# interface.net
KiCad netlist of a schematic drawn in Altium Designer
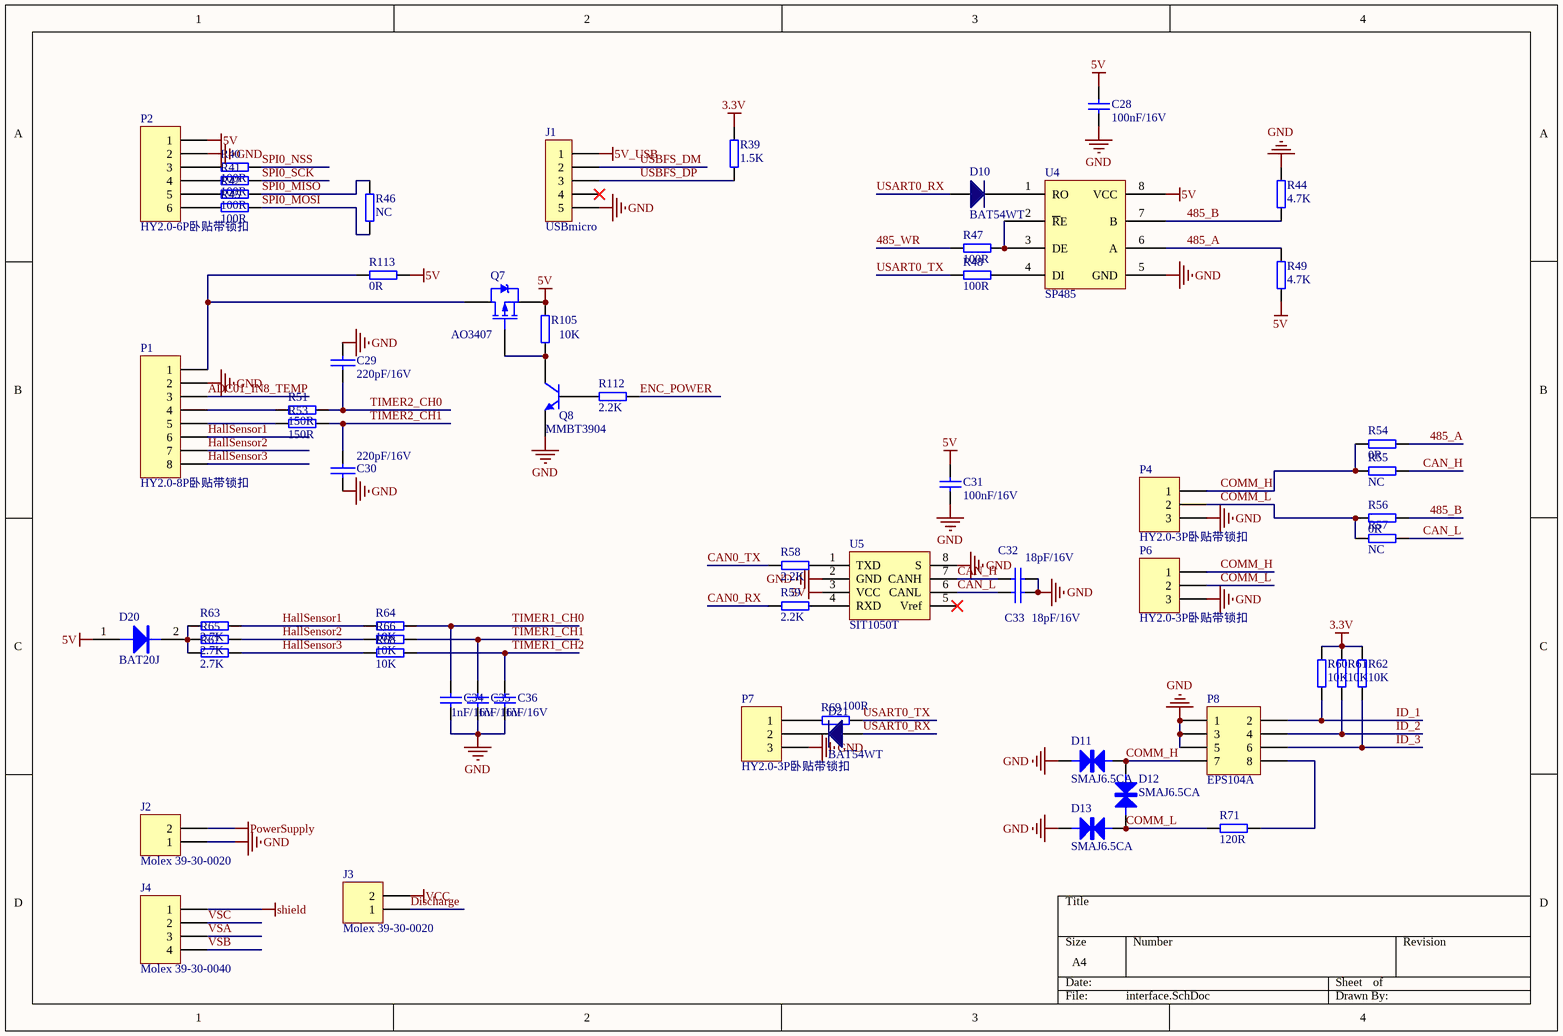
[diagram p0: interface.SchDoc]

(export (version "E")
  (design (tool "Eeschema 10.0.6"))
  (components
    (comp (ref "C28") (value "100nF/16V") (footprint "C0402") (libsource (lib "zijianku") (part "cap")))
    (comp (ref "C29")
      (value "220pF/16V")
      (footprint "C0402")
      (description "Capacitor")
      (libsource (lib "*") (part "CAP"))
    )
    (comp (ref "C30")
      (value "220pF/16V")
      (footprint "C0402")
      (description "Capacitor")
      (libsource (lib "*") (part "CAP"))
    )
    (comp (ref "C31") (value "100nF/16V") (footprint "C0402") (libsource (lib "zijianku") (part "cap")))
    (comp (ref "C32") (value "18pF/16V") (footprint "C0402") (libsource (lib "zijianku") (part "cap")))
    (comp (ref "C33") (value "18pF/16V") (footprint "C0402") (libsource (lib "zijianku") (part "cap")))
    (comp (ref "C34") (value "1nF/16V") (footprint "C0402") (libsource (lib "zijianku") (part "cap")))
    (comp (ref "C35") (value "1nF/16V") (footprint "C0402") (libsource (lib "zijianku") (part "cap")))
    (comp (ref "C36") (value "1nF/16V") (footprint "C0402") (libsource (lib "zijianku") (part "cap")))
    (comp (ref "D10")
      (value "BAT54WT")
      (footprint "SOD-523/SC-79")
      (libsource (lib "Common Device") (part "Diode"))
    )
    (comp (ref "D11")
      (value "SMAJ6.5CA")
      (footprint "DO-214AC SMA")
      (libsource (lib "zijianku") (part "Bi-DIODES"))
    )
    (comp (ref "D12")
      (value "SMAJ6.5CA")
      (footprint "DO-214AC SMA")
      (libsource (lib "") (part "Bi-DIODES_1"))
    )
    (comp (ref "D13")
      (value "SMAJ6.5CA")
      (footprint "DO-214AC SMA")
      (libsource (lib "zijianku") (part "Bi-DIODES"))
    )
    (comp (ref "D20") (value "BAT20J") (footprint "SOD-323") (libsource (lib "*") (part "DIODE")))
    (comp (ref "D21")
      (value "BAT54WT")
      (footprint "SOD-523/SC-79")
      (libsource (lib "Common Device") (part "Diode"))
    )
    (comp (ref "J1")
      (value "USBmicro")
      (footprint "USBmicro")
      (description "USB micro母座")
      (libsource (lib "*") (part "CON5"))
    )
    (comp (ref "J2")
      (value "Molex 39-30-0020")
      (footprint "Molex 39-30-0020")
      (description "Header, 2-Pin")
      (fields (field (name "PUBLISHER") "Altium Limited"))
      (libsource (lib "Common Headers") (part "Header 2"))
    )
    (comp (ref "J3")
      (value "Molex 39-30-0020")
      (footprint "Molex 39-30-0020")
      (description "Header, 2-Pin")
      (fields (field (name "PUBLISHER") "Altium Limited"))
      (libsource (lib "Common Headers") (part "Header 2"))
    )
    (comp (ref "J4")
      (value "Molex 39-30-0040")
      (footprint "Molex 39-30-0040")
      (description "Header, 4-Pin")
      (fields (field (name "PUBLISHER") "Altium Limited"))
      (libsource (lib "Common Headers") (part "Header 4"))
    )
    (comp (ref "P1")
      (value "HY2.0-8P卧贴带锁扣")
      (footprint "2.0-8PIN 卧式")
      (fields (field (name "PUBLISHER") "Altium Limited"))
      (libsource (lib "Common Headers") (part "Header 8"))
    )
    (comp (ref "P2")
      (value "HY2.0-6P卧贴带锁扣")
      (footprint "2.0-6PIN 卧式")
      (fields (field (name "PUBLISHER") "Altium Limited"))
      (libsource (lib "Common Headers") (part "Header 6"))
    )
    (comp (ref "P4")
      (value "HY2.0-3P卧贴带锁扣")
      (footprint "2.0-3PIN 卧式")
      (fields (field (name "PUBLISHER") "Altium Limited"))
      (libsource (lib "Common Headers") (part "Header 3"))
    )
    (comp (ref "P6")
      (value "HY2.0-3P卧贴带锁扣")
      (footprint "2.0-3PIN 卧式")
      (fields (field (name "PUBLISHER") "Altium Limited"))
      (libsource (lib "Common Headers") (part "Header 3"))
    )
    (comp (ref "P7")
      (value "HY2.0-3P卧贴带锁扣")
      (footprint "2.0-3PIN 卧式")
      (fields (field (name "PUBLISHER") "Altium Limited"))
      (libsource (lib "Common Headers") (part "Header 3"))
    )
    (comp (ref "P8")
      (value "EPS104A")
      (footprint "EPG104A")
      (description "侧拨程式开关 2.54间距 4PIN 品牌：台湾ECE")
      (fields (field (name "PUBLISHER") "Altium Limited"))
      (libsource (lib "Common Headers") (part "Header 4X2"))
    )
    (comp (ref "Q7")
      (value "AO3407")
      (footprint "SOT-23")
      (libsource (lib "zijianku") (part "P-channel Enhancement MOS"))
    )
    (comp (ref "Q8") (value "MMBT3904") (footprint "SOT-23") (libsource (lib "zijianku") (part "NPN")))
    (comp (ref "R39") (value "1.5K") (footprint "R0402") (libsource (lib "zijianku") (part "Resistance")))
    (comp (ref "R40") (value "100R") (footprint "R0402") (libsource (lib "zijianku") (part "Resistance")))
    (comp (ref "R41") (value "100R") (footprint "R0402") (libsource (lib "zijianku") (part "Resistance")))
    (comp (ref "R42") (value "100R") (footprint "R0402") (libsource (lib "zijianku") (part "Resistance")))
    (comp (ref "R44") (value "4.7K") (footprint "R0402") (libsource (lib "zijianku") (part "Resistance")))
    (comp (ref "R45") (value "100R") (footprint "R0402") (libsource (lib "zijianku") (part "Resistance")))
    (comp (ref "R46") (value "NC") (footprint "R0603") (libsource (lib "zijianku") (part "Resistance")))
    (comp (ref "R47") (value "100R") (footprint "R0402") (libsource (lib "zijianku") (part "Resistance")))
    (comp (ref "R48") (value "100R") (footprint "R0402") (libsource (lib "zijianku") (part "Resistance")))
    (comp (ref "R49") (value "4.7K") (footprint "R0402") (libsource (lib "zijianku") (part "Resistance")))
    (comp (ref "R51") (value "150R") (footprint "R0402") (libsource (lib "zijianku") (part "Resistance")))
    (comp (ref "R53") (value "150R") (footprint "R0402") (libsource (lib "zijianku") (part "Resistance")))
    (comp (ref "R54") (value "0R") (footprint "R0603") (libsource (lib "zijianku") (part "Resistance")))
    (comp (ref "R55") (value "NC") (footprint "R0603") (libsource (lib "zijianku") (part "Resistance")))
    (comp (ref "R56") (value "0R") (footprint "R0603") (libsource (lib "zijianku") (part "Resistance")))
    (comp (ref "R57") (value "NC") (footprint "R0603") (libsource (lib "zijianku") (part "Resistance")))
    (comp (ref "R58") (value "2.2K") (footprint "R0402") (libsource (lib "zijianku") (part "Resistance")))
    (comp (ref "R59") (value "2.2K") (footprint "R0402") (libsource (lib "zijianku") (part "Resistance")))
    (comp (ref "R60") (value "10K") (footprint "R0402") (libsource (lib "zijianku") (part "Resistance")))
    (comp (ref "R61") (value "10K") (footprint "R0402") (libsource (lib "zijianku") (part "Resistance")))
    (comp (ref "R62") (value "10K") (footprint "R0402") (libsource (lib "zijianku") (part "Resistance")))
    (comp (ref "R63") (value "2.7K") (footprint "R0402") (libsource (lib "zijianku") (part "Resistance")))
    (comp (ref "R64") (value "10K") (footprint "R0402") (libsource (lib "zijianku") (part "Resistance")))
    (comp (ref "R65") (value "2.7K") (footprint "R0402") (libsource (lib "zijianku") (part "Resistance")))
    (comp (ref "R66") (value "10K") (footprint "R0402") (libsource (lib "zijianku") (part "Resistance")))
    (comp (ref "R67") (value "2.7K") (footprint "R0402") (libsource (lib "zijianku") (part "Resistance")))
    (comp (ref "R68") (value "10K") (footprint "R0402") (libsource (lib "zijianku") (part "Resistance")))
    (comp (ref "R69") (value "100R") (footprint "R0402") (libsource (lib "zijianku") (part "Resistance")))
    (comp (ref "R71") (value "120R") (footprint "R0603") (libsource (lib "zijianku") (part "Resistance")))
    (comp (ref "R105") (value "10K") (footprint "R0402") (libsource (lib "zijianku") (part "Resistance")))
    (comp (ref "R112") (value "2.2K") (footprint "R0402") (libsource (lib "zijianku") (part "Resistance")))
    (comp (ref "R113") (value "0R") (footprint "R0805") (libsource (lib "zijianku") (part "Resistance")))
    (comp (ref "U4") (value "SP485") (footprint "SOIC-8") (libsource (lib "zijianku") (part "SP485")))
    (comp (ref "U5")
      (value "SIT1050T")
      (footprint "SOIC-8")
      (libsource (lib "Common Device") (part "TJA1050"))
    )
  )
  (nets
    (net (code "1") (name "/485_A") (class "Default")
      (node (ref "R49") (pin "2") (pintype "passive"))
      (node (ref "R54") (pin "1") (pintype "passive"))
      (node (ref "U4") (pin "6") (pinfunction "A_6") (pintype "passive"))
    )
    (net (code "2") (name "/485_B") (class "Default")
      (node (ref "R44") (pin "1") (pintype "passive"))
      (node (ref "R56") (pin "1") (pintype "passive"))
      (node (ref "U4") (pin "7") (pinfunction "B_7") (pintype "passive"))
    )
    (net (code "3") (name "/485_WR") (class "Default") (node (ref "R47") (pin "2") (pintype "passive")))
    (net (code "4") (name "/ADC01_IN8_TEMP") (class "Default")
      (node (ref "P1") (pin "3") (pinfunction "3_3") (pintype "passive"))
    )
    (net (code "5") (name "/CAN0_RX") (class "Default") (node (ref "R59") (pin "2") (pintype "passive")))
    (net (code "6") (name "/CAN0_TX") (class "Default") (node (ref "R58") (pin "2") (pintype "passive")))
    (net (code "7") (name "/CAN_H") (class "Default")
      (node (ref "C32") (pin "2") (pinfunction "1_2") (pintype "passive"))
      (node (ref "R55") (pin "1") (pintype "passive"))
      (node (ref "U5") (pin "7") (pinfunction "CANH_7") (pintype "passive"))
    )
    (net (code "8") (name "/CAN_L") (class "Default")
      (node (ref "C33") (pin "2") (pinfunction "1_2") (pintype "passive"))
      (node (ref "R57") (pin "1") (pintype "passive"))
      (node (ref "U5") (pin "6") (pinfunction "CANL_6") (pintype "passive"))
    )
    (net (code "9") (name "/COMM_H") (class "Default")
      (node (ref "D11") (pin "2") (pinfunction "Anode_2") (pintype "passive"))
      (node (ref "D12") (pin "1") (pinfunction "Anode_1") (pintype "passive"))
      (node (ref "P4") (pin "1") (pinfunction "1_1") (pintype "passive"))
      (node (ref "P6") (pin "1") (pinfunction "1_1") (pintype "passive"))
      (node (ref "P8") (pin "7") (pinfunction "7_7") (pintype "passive"))
      (node (ref "R54") (pin "2") (pintype "passive"))
      (node (ref "R55") (pin "2") (pintype "passive"))
    )
    (net (code "10") (name "/COMM_L") (class "Default")
      (node (ref "D12") (pin "2") (pinfunction "Anode_2") (pintype "passive"))
      (node (ref "D13") (pin "2") (pinfunction "Anode_2") (pintype "passive"))
      (node (ref "P4") (pin "2") (pinfunction "2_2") (pintype "passive"))
      (node (ref "P6") (pin "2") (pinfunction "2_2") (pintype "passive"))
      (node (ref "R56") (pin "2") (pintype "passive"))
      (node (ref "R57") (pin "2") (pintype "passive"))
      (node (ref "R71") (pin "2") (pintype "passive"))
    )
    (net (code "11") (name "/Discharge") (class "Default")
      (node (ref "J3") (pin "1") (pinfunction "1_1") (pintype "passive"))
    )
    (net (code "12") (name "/ENC_POWER") (class "Default") (node (ref "R112") (pin "2") (pintype "passive")))
    (net (code "13") (name "/HallSensor1") (class "Default")
      (node (ref "P1") (pin "6") (pinfunction "6_6") (pintype "passive"))
      (node (ref "R63") (pin "1") (pintype "passive"))
      (node (ref "R64") (pin "1") (pintype "passive"))
    )
    (net (code "14") (name "/HallSensor2") (class "Default")
      (node (ref "P1") (pin "7") (pinfunction "7_7") (pintype "passive"))
      (node (ref "R65") (pin "1") (pintype "passive"))
      (node (ref "R66") (pin "1") (pintype "passive"))
    )
    (net (code "15") (name "/HallSensor3") (class "Default")
      (node (ref "P1") (pin "8") (pinfunction "8_8") (pintype "passive"))
      (node (ref "R67") (pin "1") (pintype "passive"))
      (node (ref "R68") (pin "1") (pintype "passive"))
    )
    (net (code "16") (name "/ID_1") (class "Default")
      (node (ref "P8") (pin "2") (pinfunction "2_2") (pintype "passive"))
      (node (ref "R60") (pin "1") (pintype "passive"))
    )
    (net (code "17") (name "/ID_2") (class "Default")
      (node (ref "P8") (pin "4") (pinfunction "4_4") (pintype "passive"))
      (node (ref "R61") (pin "1") (pintype "passive"))
    )
    (net (code "18") (name "/ID_3") (class "Default")
      (node (ref "P8") (pin "6") (pinfunction "6_6") (pintype "passive"))
      (node (ref "R62") (pin "1") (pintype "passive"))
    )
    (net (code "19") (name "/SPI0_MISO") (class "Default")
      (node (ref "R42") (pin "1") (pintype "passive"))
      (node (ref "R46") (pin "1") (pintype "passive"))
    )
    (net (code "20") (name "/SPI0_MOSI") (class "Default")
      (node (ref "R45") (pin "1") (pintype "passive"))
      (node (ref "R46") (pin "2") (pintype "passive"))
    )
    (net (code "21") (name "/SPI0_NSS") (class "Default") (node (ref "R40") (pin "1") (pintype "passive")))
    (net (code "22") (name "/SPI0_SCK") (class "Default") (node (ref "R41") (pin "1") (pintype "passive")))
    (net (code "23") (name "/TIMER1_CH0") (class "Default")
      (node (ref "C34") (pin "1") (pinfunction "0_1") (pintype "passive"))
      (node (ref "R64") (pin "2") (pintype "passive"))
    )
    (net (code "24") (name "/TIMER1_CH1") (class "Default")
      (node (ref "C35") (pin "1") (pinfunction "0_1") (pintype "passive"))
      (node (ref "R66") (pin "2") (pintype "passive"))
    )
    (net (code "25") (name "/TIMER1_CH2") (class "Default")
      (node (ref "C36") (pin "1") (pinfunction "0_1") (pintype "passive"))
      (node (ref "R68") (pin "2") (pintype "passive"))
    )
    (net (code "26") (name "/TIMER2_CH0") (class "Default")
      (node (ref "C29") (pin "1") (pinfunction "1_1") (pintype "passive"))
      (node (ref "R51") (pin "2") (pintype "passive"))
    )
    (net (code "27") (name "/TIMER2_CH1") (class "Default")
      (node (ref "C30") (pin "2") (pinfunction "2_2") (pintype "passive"))
      (node (ref "R53") (pin "2") (pintype "passive"))
    )
    (net (code "28") (name "/USART0_RX") (class "Default")
      (node (ref "D10") (pin "1") (pinfunction "0_1") (pintype "passive"))
      (node (ref "D21") (pin "1") (pinfunction "0_1") (pintype "passive"))
    )
    (net (code "29") (name "/USART0_TX") (class "Default")
      (node (ref "R48") (pin "2") (pintype "passive"))
      (node (ref "R69") (pin "1") (pintype "passive"))
    )
    (net (code "30") (name "/USBFS_DM") (class "Default")
      (node (ref "J1") (pin "2") (pinfunction "2_2") (pintype "passive"))
    )
    (net (code "31") (name "/USBFS_DP") (class "Default")
      (node (ref "J1") (pin "3") (pinfunction "3_3") (pintype "passive"))
      (node (ref "R39") (pin "1") (pintype "passive"))
    )
    (net (code "32") (name "/VSA") (class "Default")
      (node (ref "J4") (pin "3") (pinfunction "3_3") (pintype "passive"))
    )
    (net (code "33") (name "/VSB") (class "Default")
      (node (ref "J4") (pin "4") (pinfunction "4_4") (pintype "passive"))
    )
    (net (code "34") (name "/VSC") (class "Default")
      (node (ref "J4") (pin "2") (pinfunction "2_2") (pintype "passive"))
    )
    (net (code "35") (name "3.3V") (class "Default")
      (node (ref "R39") (pin "2") (pintype "passive"))
      (node (ref "R60") (pin "2") (pintype "passive"))
      (node (ref "R61") (pin "2") (pintype "passive"))
      (node (ref "R62") (pin "2") (pintype "passive"))
    )
    (net (code "36") (name "5V") (class "Default")
      (node (ref "C28") (pin "1") (pinfunction "0_1") (pintype "passive"))
      (node (ref "C31") (pin "1") (pinfunction "0_1") (pintype "passive"))
      (node (ref "D20") (pin "1") (pinfunction "A_1") (pintype "passive"))
      (node (ref "P2") (pin "1") (pinfunction "1_1") (pintype "passive"))
      (node (ref "Q7") (pin "2") (pinfunction "S_2") (pintype "passive"))
      (node (ref "R105") (pin "2") (pintype "passive"))
      (node (ref "R113") (pin "2") (pintype "passive"))
      (node (ref "R49") (pin "1") (pintype "passive"))
      (node (ref "U4") (pin "8") (pinfunction "VCC_8") (pintype "passive"))
      (node (ref "U5") (pin "3") (pinfunction "VCC_3") (pintype "passive"))
    )
    (net (code "37") (name "5V_USB") (class "Default")
      (node (ref "J1") (pin "1") (pinfunction "1_1") (pintype "passive"))
    )
    (net (code "38") (name "GND") (class "Default")
      (node (ref "C28") (pin "2") (pinfunction "1_2") (pintype "passive"))
      (node (ref "C29") (pin "2") (pinfunction "2_2") (pintype "passive"))
      (node (ref "C30") (pin "1") (pinfunction "1_1") (pintype "passive"))
      (node (ref "C31") (pin "2") (pinfunction "1_2") (pintype "passive"))
      (node (ref "C32") (pin "1") (pinfunction "0_1") (pintype "passive"))
      (node (ref "C33") (pin "1") (pinfunction "0_1") (pintype "passive"))
      (node (ref "C34") (pin "2") (pinfunction "1_2") (pintype "passive"))
      (node (ref "C35") (pin "2") (pinfunction "1_2") (pintype "passive"))
      (node (ref "C36") (pin "2") (pinfunction "1_2") (pintype "passive"))
      (node (ref "D11") (pin "1") (pinfunction "Anode_1") (pintype "passive"))
      (node (ref "D13") (pin "1") (pinfunction "Anode_1") (pintype "passive"))
      (node (ref "J1") (pin "5") (pinfunction "5_5") (pintype "passive"))
      (node (ref "J2") (pin "1") (pinfunction "1_1") (pintype "passive"))
      (node (ref "P1") (pin "2") (pinfunction "2_2") (pintype "passive"))
      (node (ref "P2") (pin "2") (pinfunction "2_2") (pintype "passive"))
      (node (ref "P4") (pin "3") (pinfunction "3_3") (pintype "passive"))
      (node (ref "P6") (pin "3") (pinfunction "3_3") (pintype "passive"))
      (node (ref "P7") (pin "3") (pinfunction "3_3") (pintype "passive"))
      (node (ref "P8") (pin "1") (pinfunction "1_1") (pintype "passive"))
      (node (ref "P8") (pin "3") (pinfunction "3_3") (pintype "passive"))
      (node (ref "P8") (pin "5") (pinfunction "5_5") (pintype "passive"))
      (node (ref "Q8") (pin "2") (pinfunction "E_2") (pintype "passive"))
      (node (ref "R44") (pin "2") (pintype "passive"))
      (node (ref "U4") (pin "5") (pinfunction "GND_5") (pintype "passive"))
      (node (ref "U5") (pin "2") (pinfunction "GND_2") (pintype "passive"))
      (node (ref "U5") (pin "8") (pinfunction "S_8") (pintype "passive"))
    )
    (net (code "39") (name "Net-(D10-1)") (class "Default")
      (node (ref "D10") (pin "2") (pinfunction "1_2") (pintype "passive"))
      (node (ref "U4") (pin "1") (pinfunction "RO_1") (pintype "passive"))
    )
    (net (code "40") (name "Net-(D20-K)") (class "Default")
      (node (ref "D20") (pin "2") (pinfunction "K_2") (pintype "passive"))
      (node (ref "R63") (pin "2") (pintype "passive"))
      (node (ref "R65") (pin "2") (pintype "passive"))
      (node (ref "R67") (pin "2") (pintype "passive"))
    )
    (net (code "41") (name "Net-(D21-1)") (class "Default")
      (node (ref "D21") (pin "2") (pinfunction "1_2") (pintype "passive"))
      (node (ref "P7") (pin "2") (pinfunction "2_2") (pintype "passive"))
    )
    (net (code "42") (name "Net-(P1-Pad4)") (class "Default")
      (node (ref "P1") (pin "4") (pinfunction "4_4") (pintype "passive"))
      (node (ref "R51") (pin "1") (pintype "passive"))
    )
    (net (code "43") (name "Net-(P1-Pad5)") (class "Default")
      (node (ref "P1") (pin "5") (pinfunction "5_5") (pintype "passive"))
      (node (ref "R53") (pin "1") (pintype "passive"))
    )
    (net (code "44") (name "Net-(P2-Pad3)") (class "Default")
      (node (ref "P2") (pin "3") (pinfunction "3_3") (pintype "passive"))
      (node (ref "R40") (pin "2") (pintype "passive"))
    )
    (net (code "45") (name "Net-(P2-Pad4)") (class "Default")
      (node (ref "P2") (pin "4") (pinfunction "4_4") (pintype "passive"))
      (node (ref "R41") (pin "2") (pintype "passive"))
    )
    (net (code "46") (name "Net-(P2-Pad5)") (class "Default")
      (node (ref "P2") (pin "5") (pinfunction "5_5") (pintype "passive"))
      (node (ref "R42") (pin "2") (pintype "passive"))
    )
    (net (code "47") (name "Net-(P2-Pad6)") (class "Default")
      (node (ref "P2") (pin "6") (pinfunction "6_6") (pintype "passive"))
      (node (ref "R45") (pin "2") (pintype "passive"))
    )
    (net (code "48") (name "Net-(P7-Pad1)") (class "Default")
      (node (ref "P7") (pin "1") (pinfunction "1_1") (pintype "passive"))
      (node (ref "R69") (pin "2") (pintype "passive"))
    )
    (net (code "49") (name "Net-(P8-Pad8)") (class "Default")
      (node (ref "P8") (pin "8") (pinfunction "8_8") (pintype "passive"))
      (node (ref "R71") (pin "1") (pintype "passive"))
    )
    (net (code "50") (name "Net-(Q7-D)") (class "Default")
      (node (ref "P1") (pin "1") (pinfunction "1_1") (pintype "passive"))
      (node (ref "Q7") (pin "3") (pinfunction "D_3") (pintype "passive"))
      (node (ref "R113") (pin "1") (pintype "passive"))
    )
    (net (code "51") (name "Net-(Q7-G)") (class "Default")
      (node (ref "Q7") (pin "1") (pinfunction "G_1") (pintype "passive"))
      (node (ref "Q8") (pin "3") (pinfunction "C_3") (pintype "passive"))
      (node (ref "R105") (pin "1") (pintype "passive"))
    )
    (net (code "52") (name "Net-(Q8-B)") (class "Default")
      (node (ref "Q8") (pin "1") (pinfunction "B_1") (pintype "passive"))
      (node (ref "R112") (pin "1") (pintype "passive"))
    )
    (net (code "53") (name "Net-(U4-DE)") (class "Default")
      (node (ref "R47") (pin "1") (pintype "passive"))
      (node (ref "U4") (pin "2") (pinfunction "~{R}E_2") (pintype "passive"))
      (node (ref "U4") (pin "3") (pinfunction "DE_3") (pintype "passive"))
    )
    (net (code "54") (name "Net-(U4-DI)") (class "Default")
      (node (ref "R48") (pin "1") (pintype "passive"))
      (node (ref "U4") (pin "4") (pinfunction "DI_4") (pintype "passive"))
    )
    (net (code "55") (name "Net-(U5-RXD)") (class "Default")
      (node (ref "R59") (pin "1") (pintype "passive"))
      (node (ref "U5") (pin "4") (pinfunction "RXD_4") (pintype "passive"))
    )
    (net (code "56") (name "Net-(U5-TXD)") (class "Default")
      (node (ref "R58") (pin "1") (pintype "passive"))
      (node (ref "U5") (pin "1") (pinfunction "TXD_1") (pintype "passive"))
    )
    (net (code "57") (name "PowerSupply") (class "Default")
      (node (ref "J2") (pin "2") (pinfunction "2_2") (pintype "passive"))
    )
    (net (code "58") (name "VCC") (class "Default")
      (node (ref "J3") (pin "2") (pinfunction "2_2") (pintype "passive"))
    )
    (net (code "59") (name "shield") (class "Default")
      (node (ref "J4") (pin "1") (pinfunction "1_1") (pintype "passive"))
    )
    (net (code "60") (name "unconnected-(J1-Pad4)") (class "Default")
      (node (ref "J1") (pin "4") (pinfunction "4_4") (pintype "passive+no_connect"))
    )
    (net (code "61") (name "unconnected-(U5-Vref-Pad5)") (class "Default")
      (node (ref "U5") (pin "5") (pinfunction "Vref_5") (pintype "passive+no_connect"))
    )
  )
)
